# CONTROLADOR-V1-RELES.net
KiCad netlist of a schematic drawn in Altium Designer
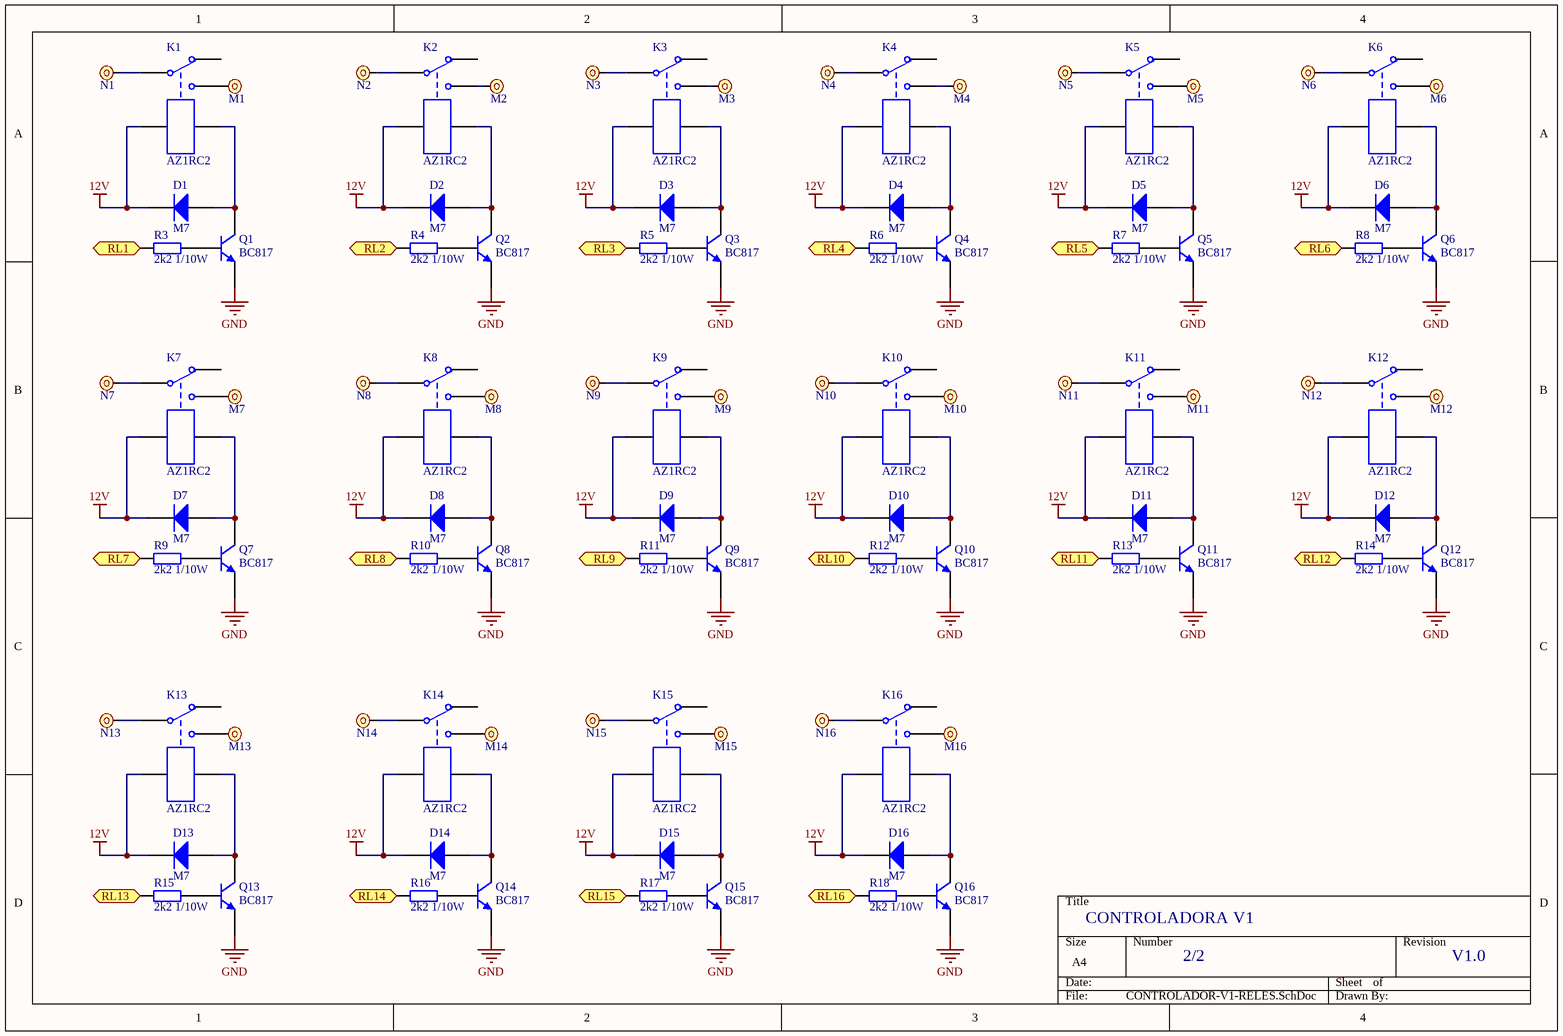
[diagram p0: CONTROLADOR-V1-RELES.SchDoc]

(export (version "E")
  (design (tool "Eeschema 10.0.6"))
  (components
    (comp (ref "D1")
      (value "M7")
      (footprint "Lib SMD:DO-214AC - SMA")
      (description "DIODE GEN PURP 1KV 1A DO214AC")
      (fields (field (name "MANUFACTURER") "Kingtronics"))
      (libsource (lib "Lib SMD") (part "Diodo M7"))
    )
    (comp (ref "D2")
      (value "M7")
      (footprint "Lib SMD:DO-214AC - SMA")
      (description "DIODE GEN PURP 1KV 1A DO214AC")
      (fields (field (name "MANUFACTURER") "Kingtronics"))
      (libsource (lib "Lib SMD") (part "Diodo M7"))
    )
    (comp (ref "D3")
      (value "M7")
      (footprint "Lib SMD:DO-214AC - SMA")
      (description "DIODE GEN PURP 1KV 1A DO214AC")
      (fields (field (name "MANUFACTURER") "Kingtronics"))
      (libsource (lib "Lib SMD") (part "Diodo M7"))
    )
    (comp (ref "D4")
      (value "M7")
      (footprint "Lib SMD:DO-214AC - SMA")
      (description "DIODE GEN PURP 1KV 1A DO214AC")
      (fields (field (name "MANUFACTURER") "Kingtronics"))
      (libsource (lib "Lib SMD") (part "Diodo M7"))
    )
    (comp (ref "D5")
      (value "M7")
      (footprint "Lib SMD:DO-214AC - SMA")
      (description "DIODE GEN PURP 1KV 1A DO214AC")
      (fields (field (name "MANUFACTURER") "Kingtronics"))
      (libsource (lib "Lib SMD") (part "Diodo M7"))
    )
    (comp (ref "D6")
      (value "M7")
      (footprint "Lib SMD:DO-214AC - SMA")
      (description "DIODE GEN PURP 1KV 1A DO214AC")
      (fields (field (name "MANUFACTURER") "Kingtronics"))
      (libsource (lib "Lib SMD") (part "Diodo M7"))
    )
    (comp (ref "D7")
      (value "M7")
      (footprint "Lib SMD:DO-214AC - SMA")
      (description "DIODE GEN PURP 1KV 1A DO214AC")
      (fields (field (name "MANUFACTURER") "Kingtronics"))
      (libsource (lib "Lib SMD") (part "Diodo M7"))
    )
    (comp (ref "D8")
      (value "M7")
      (footprint "Lib SMD:DO-214AC - SMA")
      (description "DIODE GEN PURP 1KV 1A DO214AC")
      (fields (field (name "MANUFACTURER") "Kingtronics"))
      (libsource (lib "Lib SMD") (part "Diodo M7"))
    )
    (comp (ref "D9")
      (value "M7")
      (footprint "Lib SMD:DO-214AC - SMA")
      (description "DIODE GEN PURP 1KV 1A DO214AC")
      (fields (field (name "MANUFACTURER") "Kingtronics"))
      (libsource (lib "Lib SMD") (part "Diodo M7"))
    )
    (comp (ref "D10")
      (value "M7")
      (footprint "Lib SMD:DO-214AC - SMA")
      (description "DIODE GEN PURP 1KV 1A DO214AC")
      (fields (field (name "MANUFACTURER") "Kingtronics"))
      (libsource (lib "Lib SMD") (part "Diodo M7"))
    )
    (comp (ref "D11")
      (value "M7")
      (footprint "Lib SMD:DO-214AC - SMA")
      (description "DIODE GEN PURP 1KV 1A DO214AC")
      (fields (field (name "MANUFACTURER") "Kingtronics"))
      (libsource (lib "Lib SMD") (part "Diodo M7"))
    )
    (comp (ref "D12")
      (value "M7")
      (footprint "Lib SMD:DO-214AC - SMA")
      (description "DIODE GEN PURP 1KV 1A DO214AC")
      (fields (field (name "MANUFACTURER") "Kingtronics"))
      (libsource (lib "Lib SMD") (part "Diodo M7"))
    )
    (comp (ref "D13")
      (value "M7")
      (footprint "Lib SMD:DO-214AC - SMA")
      (description "DIODE GEN PURP 1KV 1A DO214AC")
      (fields (field (name "MANUFACTURER") "Kingtronics"))
      (libsource (lib "Lib SMD") (part "Diodo M7"))
    )
    (comp (ref "D14")
      (value "M7")
      (footprint "Lib SMD:DO-214AC - SMA")
      (description "DIODE GEN PURP 1KV 1A DO214AC")
      (fields (field (name "MANUFACTURER") "Kingtronics"))
      (libsource (lib "Lib SMD") (part "Diodo M7"))
    )
    (comp (ref "D15")
      (value "M7")
      (footprint "Lib SMD:DO-214AC - SMA")
      (description "DIODE GEN PURP 1KV 1A DO214AC")
      (fields (field (name "MANUFACTURER") "Kingtronics"))
      (libsource (lib "Lib SMD") (part "Diodo M7"))
    )
    (comp (ref "D16")
      (value "M7")
      (footprint "Lib SMD:DO-214AC - SMA")
      (description "DIODE GEN PURP 1KV 1A DO214AC")
      (fields (field (name "MANUFACTURER") "Kingtronics"))
      (libsource (lib "Lib SMD") (part "Diodo M7"))
    )
    (comp (ref "K1")
      (value "AZ1RC2")
      (footprint "Lib PTH:RELE SPDT")
      (description "RELAY GEN PURPOSE SPDT 10A 12V")
      (fields (field (name "MANUFACTURER") "Metaltex"))
      (libsource (lib "Lib PTH") (part "Rele AZ1RC2"))
    )
    (comp (ref "K2")
      (value "AZ1RC2")
      (footprint "Lib PTH:RELE SPDT")
      (description "RELAY GEN PURPOSE SPDT 10A 12V")
      (fields (field (name "MANUFACTURER") "Metaltex"))
      (libsource (lib "Lib PTH") (part "Rele AZ1RC2"))
    )
    (comp (ref "K3")
      (value "AZ1RC2")
      (footprint "Lib PTH:RELE SPDT")
      (description "RELAY GEN PURPOSE SPDT 10A 12V")
      (fields (field (name "MANUFACTURER") "Metaltex"))
      (libsource (lib "Lib PTH") (part "Rele AZ1RC2"))
    )
    (comp (ref "K4")
      (value "AZ1RC2")
      (footprint "Lib PTH:RELE SPDT")
      (description "RELAY GEN PURPOSE SPDT 10A 12V")
      (fields (field (name "MANUFACTURER") "Metaltex"))
      (libsource (lib "Lib PTH") (part "Rele AZ1RC2"))
    )
    (comp (ref "K5")
      (value "AZ1RC2")
      (footprint "Lib PTH:RELE SPDT")
      (description "RELAY GEN PURPOSE SPDT 10A 12V")
      (fields (field (name "MANUFACTURER") "Metaltex"))
      (libsource (lib "Lib PTH") (part "Rele AZ1RC2"))
    )
    (comp (ref "K6")
      (value "AZ1RC2")
      (footprint "Lib PTH:RELE SPDT")
      (description "RELAY GEN PURPOSE SPDT 10A 12V")
      (fields (field (name "MANUFACTURER") "Metaltex"))
      (libsource (lib "Lib PTH") (part "Rele AZ1RC2"))
    )
    (comp (ref "K7")
      (value "AZ1RC2")
      (footprint "Lib PTH:RELE SPDT")
      (description "RELAY GEN PURPOSE SPDT 10A 12V")
      (fields (field (name "MANUFACTURER") "Metaltex"))
      (libsource (lib "Lib PTH") (part "Rele AZ1RC2"))
    )
    (comp (ref "K8")
      (value "AZ1RC2")
      (footprint "Lib PTH:RELE SPDT")
      (description "RELAY GEN PURPOSE SPDT 10A 12V")
      (fields (field (name "MANUFACTURER") "Metaltex"))
      (libsource (lib "Lib PTH") (part "Rele AZ1RC2"))
    )
    (comp (ref "K9")
      (value "AZ1RC2")
      (footprint "Lib PTH:RELE SPDT")
      (description "RELAY GEN PURPOSE SPDT 10A 12V")
      (fields (field (name "MANUFACTURER") "Metaltex"))
      (libsource (lib "Lib PTH") (part "Rele AZ1RC2"))
    )
    (comp (ref "K10")
      (value "AZ1RC2")
      (footprint "Lib PTH:RELE SPDT")
      (description "RELAY GEN PURPOSE SPDT 10A 12V")
      (fields (field (name "MANUFACTURER") "Metaltex"))
      (libsource (lib "Lib PTH") (part "Rele AZ1RC2"))
    )
    (comp (ref "K11")
      (value "AZ1RC2")
      (footprint "Lib PTH:RELE SPDT")
      (description "RELAY GEN PURPOSE SPDT 10A 12V")
      (fields (field (name "MANUFACTURER") "Metaltex"))
      (libsource (lib "Lib PTH") (part "Rele AZ1RC2"))
    )
    (comp (ref "K12")
      (value "AZ1RC2")
      (footprint "Lib PTH:RELE SPDT")
      (description "RELAY GEN PURPOSE SPDT 10A 12V")
      (fields (field (name "MANUFACTURER") "Metaltex"))
      (libsource (lib "Lib PTH") (part "Rele AZ1RC2"))
    )
    (comp (ref "K13")
      (value "AZ1RC2")
      (footprint "Lib PTH:RELE SPDT")
      (description "RELAY GEN PURPOSE SPDT 10A 12V")
      (fields (field (name "MANUFACTURER") "Metaltex"))
      (libsource (lib "Lib PTH") (part "Rele AZ1RC2"))
    )
    (comp (ref "K14")
      (value "AZ1RC2")
      (footprint "Lib PTH:RELE SPDT")
      (description "RELAY GEN PURPOSE SPDT 10A 12V")
      (fields (field (name "MANUFACTURER") "Metaltex"))
      (libsource (lib "Lib PTH") (part "Rele AZ1RC2"))
    )
    (comp (ref "K15")
      (value "AZ1RC2")
      (footprint "Lib PTH:RELE SPDT")
      (description "RELAY GEN PURPOSE SPDT 10A 12V")
      (fields (field (name "MANUFACTURER") "Metaltex"))
      (libsource (lib "Lib PTH") (part "Rele AZ1RC2"))
    )
    (comp (ref "K16")
      (value "AZ1RC2")
      (footprint "Lib PTH:RELE SPDT")
      (description "RELAY GEN PURPOSE SPDT 10A 12V")
      (fields (field (name "MANUFACTURER") "Metaltex"))
      (libsource (lib "Lib PTH") (part "Rele AZ1RC2"))
    )
    (comp (ref "M1")
      (value "PAD 1.5x3mm")
      (footprint "Lib PTH:PAD 1.5x3mm")
      (description "PAD")
      (libsource (lib "Lib PTH") (part "PAD 1.5x3mm"))
    )
    (comp (ref "M2")
      (value "PAD 1.5x3mm")
      (footprint "Lib PTH:PAD 1.5x3mm")
      (description "PAD")
      (libsource (lib "Lib PTH") (part "PAD 1.5x3mm"))
    )
    (comp (ref "M3")
      (value "PAD 1.5x3mm")
      (footprint "Lib PTH:PAD 1.5x3mm")
      (description "PAD")
      (libsource (lib "Lib PTH") (part "PAD 1.5x3mm"))
    )
    (comp (ref "M4")
      (value "PAD 1.5x3mm")
      (footprint "Lib PTH:PAD 1.5x3mm")
      (description "PAD")
      (libsource (lib "Lib PTH") (part "PAD 1.5x3mm"))
    )
    (comp (ref "M5")
      (value "PAD 1.5x3mm")
      (footprint "Lib PTH:PAD 1.5x3mm")
      (description "PAD")
      (libsource (lib "Lib PTH") (part "PAD 1.5x3mm"))
    )
    (comp (ref "M6")
      (value "PAD 1.5x3mm")
      (footprint "Lib PTH:PAD 1.5x3mm")
      (description "PAD")
      (libsource (lib "Lib PTH") (part "PAD 1.5x3mm"))
    )
    (comp (ref "M7")
      (value "PAD 1.5x3mm")
      (footprint "Lib PTH:PAD 1.5x3mm")
      (description "PAD")
      (libsource (lib "Lib PTH") (part "PAD 1.5x3mm"))
    )
    (comp (ref "M8")
      (value "PAD 1.5x3mm")
      (footprint "Lib PTH:PAD 1.5x3mm")
      (description "PAD")
      (libsource (lib "Lib PTH") (part "PAD 1.5x3mm"))
    )
    (comp (ref "M9")
      (value "PAD 1.5x3mm")
      (footprint "Lib PTH:PAD 1.5x3mm")
      (description "PAD")
      (libsource (lib "Lib PTH") (part "PAD 1.5x3mm"))
    )
    (comp (ref "M10")
      (value "PAD 1.5x3mm")
      (footprint "Lib PTH:PAD 1.5x3mm")
      (description "PAD")
      (libsource (lib "Lib PTH") (part "PAD 1.5x3mm"))
    )
    (comp (ref "M11")
      (value "PAD 1.5x3mm")
      (footprint "Lib PTH:PAD 1.5x3mm")
      (description "PAD")
      (libsource (lib "Lib PTH") (part "PAD 1.5x3mm"))
    )
    (comp (ref "M12")
      (value "PAD 1.5x3mm")
      (footprint "Lib PTH:PAD 1.5x3mm")
      (description "PAD")
      (libsource (lib "Lib PTH") (part "PAD 1.5x3mm"))
    )
    (comp (ref "M13")
      (value "PAD 1.5x3mm")
      (footprint "Lib PTH:PAD 1.5x3mm")
      (description "PAD")
      (libsource (lib "Lib PTH") (part "PAD 1.5x3mm"))
    )
    (comp (ref "M14")
      (value "PAD 1.5x3mm")
      (footprint "Lib PTH:PAD 1.5x3mm")
      (description "PAD")
      (libsource (lib "Lib PTH") (part "PAD 1.5x3mm"))
    )
    (comp (ref "M15")
      (value "PAD 1.5x3mm")
      (footprint "Lib PTH:PAD 1.5x3mm")
      (description "PAD")
      (libsource (lib "Lib PTH") (part "PAD 1.5x3mm"))
    )
    (comp (ref "M16")
      (value "PAD 1.5x3mm")
      (footprint "Lib PTH:PAD 1.5x3mm")
      (description "PAD")
      (libsource (lib "Lib PTH") (part "PAD 1.5x3mm"))
    )
    (comp (ref "N1")
      (value "PAD 1.5x3mm")
      (footprint "Lib PTH:PAD 1.5x3mm")
      (description "PAD")
      (libsource (lib "Lib PTH") (part "PAD 1.5x3mm"))
    )
    (comp (ref "N2")
      (value "PAD 1.5x3mm")
      (footprint "Lib PTH:PAD 1.5x3mm")
      (description "PAD")
      (libsource (lib "Lib PTH") (part "PAD 1.5x3mm"))
    )
    (comp (ref "N3")
      (value "PAD 1.5x3mm")
      (footprint "Lib PTH:PAD 1.5x3mm")
      (description "PAD")
      (libsource (lib "Lib PTH") (part "PAD 1.5x3mm"))
    )
    (comp (ref "N4")
      (value "PAD 1.5x3mm")
      (footprint "Lib PTH:PAD 1.5x3mm")
      (description "PAD")
      (libsource (lib "Lib PTH") (part "PAD 1.5x3mm"))
    )
    (comp (ref "N5")
      (value "PAD 1.5x3mm")
      (footprint "Lib PTH:PAD 1.5x3mm")
      (description "PAD")
      (libsource (lib "Lib PTH") (part "PAD 1.5x3mm"))
    )
    (comp (ref "N6")
      (value "PAD 1.5x3mm")
      (footprint "Lib PTH:PAD 1.5x3mm")
      (description "PAD")
      (libsource (lib "Lib PTH") (part "PAD 1.5x3mm"))
    )
    (comp (ref "N7")
      (value "PAD 1.5x3mm")
      (footprint "Lib PTH:PAD 1.5x3mm")
      (description "PAD")
      (libsource (lib "Lib PTH") (part "PAD 1.5x3mm"))
    )
    (comp (ref "N8")
      (value "PAD 1.5x3mm")
      (footprint "Lib PTH:PAD 1.5x3mm")
      (description "PAD")
      (libsource (lib "Lib PTH") (part "PAD 1.5x3mm"))
    )
    (comp (ref "N9")
      (value "PAD 1.5x3mm")
      (footprint "Lib PTH:PAD 1.5x3mm")
      (description "PAD")
      (libsource (lib "Lib PTH") (part "PAD 1.5x3mm"))
    )
    (comp (ref "N10")
      (value "PAD 1.5x3mm")
      (footprint "Lib PTH:PAD 1.5x3mm")
      (description "PAD")
      (libsource (lib "Lib PTH") (part "PAD 1.5x3mm"))
    )
    (comp (ref "N11")
      (value "PAD 1.5x3mm")
      (footprint "Lib PTH:PAD 1.5x3mm")
      (description "PAD")
      (libsource (lib "Lib PTH") (part "PAD 1.5x3mm"))
    )
    (comp (ref "N12")
      (value "PAD 1.5x3mm")
      (footprint "Lib PTH:PAD 1.5x3mm")
      (description "PAD")
      (libsource (lib "Lib PTH") (part "PAD 1.5x3mm"))
    )
    (comp (ref "N13")
      (value "PAD 1.5x3mm")
      (footprint "Lib PTH:PAD 1.5x3mm")
      (description "PAD")
      (libsource (lib "Lib PTH") (part "PAD 1.5x3mm"))
    )
    (comp (ref "N14")
      (value "PAD 1.5x3mm")
      (footprint "Lib PTH:PAD 1.5x3mm")
      (description "PAD")
      (libsource (lib "Lib PTH") (part "PAD 1.5x3mm"))
    )
    (comp (ref "N15")
      (value "PAD 1.5x3mm")
      (footprint "Lib PTH:PAD 1.5x3mm")
      (description "PAD")
      (libsource (lib "Lib PTH") (part "PAD 1.5x3mm"))
    )
    (comp (ref "N16")
      (value "PAD 1.5x3mm")
      (footprint "Lib PTH:PAD 1.5x3mm")
      (description "PAD")
      (libsource (lib "Lib PTH") (part "PAD 1.5x3mm"))
    )
    (comp (ref "Q1")
      (value "BC817")
      (footprint "Lib SMD:SOT23-3N")
      (description "TRANS NPN 45V 0.5A SOT23")
      (fields
        (field (name "MANUFACTURER") "ON Semiconductor")
        (field (name "MANUFACTURER PART NUMBER") "BC817-25LT1G")
      )
      (libsource (lib "Lib SMD") (part "Transistor NPN BC817"))
    )
    (comp (ref "Q2")
      (value "BC817")
      (footprint "Lib SMD:SOT23-3N")
      (description "TRANS NPN 45V 0.5A SOT23")
      (fields
        (field (name "MANUFACTURER") "ON Semiconductor")
        (field (name "MANUFACTURER PART NUMBER") "BC817-25LT1G")
      )
      (libsource (lib "Lib SMD") (part "Transistor NPN BC817"))
    )
    (comp (ref "Q3")
      (value "BC817")
      (footprint "Lib SMD:SOT23-3N")
      (description "TRANS NPN 45V 0.5A SOT23")
      (fields
        (field (name "MANUFACTURER") "ON Semiconductor")
        (field (name "MANUFACTURER PART NUMBER") "BC817-25LT1G")
      )
      (libsource (lib "Lib SMD") (part "Transistor NPN BC817"))
    )
    (comp (ref "Q4")
      (value "BC817")
      (footprint "Lib SMD:SOT23-3N")
      (description "TRANS NPN 45V 0.5A SOT23")
      (fields
        (field (name "MANUFACTURER") "ON Semiconductor")
        (field (name "MANUFACTURER PART NUMBER") "BC817-25LT1G")
      )
      (libsource (lib "Lib SMD") (part "Transistor NPN BC817"))
    )
    (comp (ref "Q5")
      (value "BC817")
      (footprint "Lib SMD:SOT23-3N")
      (description "TRANS NPN 45V 0.5A SOT23")
      (fields
        (field (name "MANUFACTURER") "ON Semiconductor")
        (field (name "MANUFACTURER PART NUMBER") "BC817-25LT1G")
      )
      (libsource (lib "Lib SMD") (part "Transistor NPN BC817"))
    )
    (comp (ref "Q6")
      (value "BC817")
      (footprint "Lib SMD:SOT23-3N")
      (description "TRANS NPN 45V 0.5A SOT23")
      (fields
        (field (name "MANUFACTURER") "ON Semiconductor")
        (field (name "MANUFACTURER PART NUMBER") "BC817-25LT1G")
      )
      (libsource (lib "Lib SMD") (part "Transistor NPN BC817"))
    )
    (comp (ref "Q7")
      (value "BC817")
      (footprint "Lib SMD:SOT23-3N")
      (description "TRANS NPN 45V 0.5A SOT23")
      (fields
        (field (name "MANUFACTURER") "ON Semiconductor")
        (field (name "MANUFACTURER PART NUMBER") "BC817-25LT1G")
      )
      (libsource (lib "Lib SMD") (part "Transistor NPN BC817"))
    )
    (comp (ref "Q8")
      (value "BC817")
      (footprint "Lib SMD:SOT23-3N")
      (description "TRANS NPN 45V 0.5A SOT23")
      (fields
        (field (name "MANUFACTURER") "ON Semiconductor")
        (field (name "MANUFACTURER PART NUMBER") "BC817-25LT1G")
      )
      (libsource (lib "Lib SMD") (part "Transistor NPN BC817"))
    )
    (comp (ref "Q9")
      (value "BC817")
      (footprint "Lib SMD:SOT23-3N")
      (description "TRANS NPN 45V 0.5A SOT23")
      (fields
        (field (name "MANUFACTURER") "ON Semiconductor")
        (field (name "MANUFACTURER PART NUMBER") "BC817-25LT1G")
      )
      (libsource (lib "Lib SMD") (part "Transistor NPN BC817"))
    )
    (comp (ref "Q10")
      (value "BC817")
      (footprint "Lib SMD:SOT23-3N")
      (description "TRANS NPN 45V 0.5A SOT23")
      (fields
        (field (name "MANUFACTURER") "ON Semiconductor")
        (field (name "MANUFACTURER PART NUMBER") "BC817-25LT1G")
      )
      (libsource (lib "Lib SMD") (part "Transistor NPN BC817"))
    )
    (comp (ref "Q11")
      (value "BC817")
      (footprint "Lib SMD:SOT23-3N")
      (description "TRANS NPN 45V 0.5A SOT23")
      (fields
        (field (name "MANUFACTURER") "ON Semiconductor")
        (field (name "MANUFACTURER PART NUMBER") "BC817-25LT1G")
      )
      (libsource (lib "Lib SMD") (part "Transistor NPN BC817"))
    )
    (comp (ref "Q12")
      (value "BC817")
      (footprint "Lib SMD:SOT23-3N")
      (description "TRANS NPN 45V 0.5A SOT23")
      (fields
        (field (name "MANUFACTURER") "ON Semiconductor")
        (field (name "MANUFACTURER PART NUMBER") "BC817-25LT1G")
      )
      (libsource (lib "Lib SMD") (part "Transistor NPN BC817"))
    )
    (comp (ref "Q13")
      (value "BC817")
      (footprint "Lib SMD:SOT23-3N")
      (description "TRANS NPN 45V 0.5A SOT23")
      (fields
        (field (name "MANUFACTURER") "ON Semiconductor")
        (field (name "MANUFACTURER PART NUMBER") "BC817-25LT1G")
      )
      (libsource (lib "Lib SMD") (part "Transistor NPN BC817"))
    )
    (comp (ref "Q14")
      (value "BC817")
      (footprint "Lib SMD:SOT23-3N")
      (description "TRANS NPN 45V 0.5A SOT23")
      (fields
        (field (name "MANUFACTURER") "ON Semiconductor")
        (field (name "MANUFACTURER PART NUMBER") "BC817-25LT1G")
      )
      (libsource (lib "Lib SMD") (part "Transistor NPN BC817"))
    )
    (comp (ref "Q15")
      (value "BC817")
      (footprint "Lib SMD:SOT23-3N")
      (description "TRANS NPN 45V 0.5A SOT23")
      (fields
        (field (name "MANUFACTURER") "ON Semiconductor")
        (field (name "MANUFACTURER PART NUMBER") "BC817-25LT1G")
      )
      (libsource (lib "Lib SMD") (part "Transistor NPN BC817"))
    )
    (comp (ref "Q16")
      (value "BC817")
      (footprint "Lib SMD:SOT23-3N")
      (description "TRANS NPN 45V 0.5A SOT23")
      (fields
        (field (name "MANUFACTURER") "ON Semiconductor")
        (field (name "MANUFACTURER PART NUMBER") "BC817-25LT1G")
      )
      (libsource (lib "Lib SMD") (part "Transistor NPN BC817"))
    )
    (comp (ref "R3")
      (value "2k2 1/10W")
      (footprint "Lib SMD:RESC0603N")
      (description "RES SMD 2.2K OHM 5% 1/10W 0603")
      (fields
        (field (name "MANUFACTURER") "Stackpole Electronics Inc.")
        (field (name "MANUFACTURER PART NUMBER") "RMCF0603JT2K20")
      )
      (libsource (lib "Lib SMD") (part "Res 2k2 1/10W 5% 0603"))
    )
    (comp (ref "R4")
      (value "2k2 1/10W")
      (footprint "Lib SMD:RESC0603N")
      (description "RES SMD 2.2K OHM 5% 1/10W 0603")
      (fields
        (field (name "MANUFACTURER") "Stackpole Electronics Inc.")
        (field (name "MANUFACTURER PART NUMBER") "RMCF0603JT2K20")
      )
      (libsource (lib "Lib SMD") (part "Res 2k2 1/10W 5% 0603"))
    )
    (comp (ref "R5")
      (value "2k2 1/10W")
      (footprint "Lib SMD:RESC0603N")
      (description "RES SMD 2.2K OHM 5% 1/10W 0603")
      (fields
        (field (name "MANUFACTURER") "Stackpole Electronics Inc.")
        (field (name "MANUFACTURER PART NUMBER") "RMCF0603JT2K20")
      )
      (libsource (lib "Lib SMD") (part "Res 2k2 1/10W 5% 0603"))
    )
    (comp (ref "R6")
      (value "2k2 1/10W")
      (footprint "Lib SMD:RESC0603N")
      (description "RES SMD 2.2K OHM 5% 1/10W 0603")
      (fields
        (field (name "MANUFACTURER") "Stackpole Electronics Inc.")
        (field (name "MANUFACTURER PART NUMBER") "RMCF0603JT2K20")
      )
      (libsource (lib "Lib SMD") (part "Res 2k2 1/10W 5% 0603"))
    )
    (comp (ref "R7")
      (value "2k2 1/10W")
      (footprint "Lib SMD:RESC0603N")
      (description "RES SMD 2.2K OHM 5% 1/10W 0603")
      (fields
        (field (name "MANUFACTURER") "Stackpole Electronics Inc.")
        (field (name "MANUFACTURER PART NUMBER") "RMCF0603JT2K20")
      )
      (libsource (lib "Lib SMD") (part "Res 2k2 1/10W 5% 0603"))
    )
    (comp (ref "R8")
      (value "2k2 1/10W")
      (footprint "Lib SMD:RESC0603N")
      (description "RES SMD 2.2K OHM 5% 1/10W 0603")
      (fields
        (field (name "MANUFACTURER") "Stackpole Electronics Inc.")
        (field (name "MANUFACTURER PART NUMBER") "RMCF0603JT2K20")
      )
      (libsource (lib "Lib SMD") (part "Res 2k2 1/10W 5% 0603"))
    )
    (comp (ref "R9")
      (value "2k2 1/10W")
      (footprint "Lib SMD:RESC0603N")
      (description "RES SMD 2.2K OHM 5% 1/10W 0603")
      (fields
        (field (name "MANUFACTURER") "Stackpole Electronics Inc.")
        (field (name "MANUFACTURER PART NUMBER") "RMCF0603JT2K20")
      )
      (libsource (lib "Lib SMD") (part "Res 2k2 1/10W 5% 0603"))
    )
    (comp (ref "R10")
      (value "2k2 1/10W")
      (footprint "Lib SMD:RESC0603N")
      (description "RES SMD 2.2K OHM 5% 1/10W 0603")
      (fields
        (field (name "MANUFACTURER") "Stackpole Electronics Inc.")
        (field (name "MANUFACTURER PART NUMBER") "RMCF0603JT2K20")
      )
      (libsource (lib "Lib SMD") (part "Res 2k2 1/10W 5% 0603"))
    )
    (comp (ref "R11")
      (value "2k2 1/10W")
      (footprint "Lib SMD:RESC0603N")
      (description "RES SMD 2.2K OHM 5% 1/10W 0603")
      (fields
        (field (name "MANUFACTURER") "Stackpole Electronics Inc.")
        (field (name "MANUFACTURER PART NUMBER") "RMCF0603JT2K20")
      )
      (libsource (lib "Lib SMD") (part "Res 2k2 1/10W 5% 0603"))
    )
    (comp (ref "R12")
      (value "2k2 1/10W")
      (footprint "Lib SMD:RESC0603N")
      (description "RES SMD 2.2K OHM 5% 1/10W 0603")
      (fields
        (field (name "MANUFACTURER") "Stackpole Electronics Inc.")
        (field (name "MANUFACTURER PART NUMBER") "RMCF0603JT2K20")
      )
      (libsource (lib "Lib SMD") (part "Res 2k2 1/10W 5% 0603"))
    )
    (comp (ref "R13")
      (value "2k2 1/10W")
      (footprint "Lib SMD:RESC0603N")
      (description "RES SMD 2.2K OHM 5% 1/10W 0603")
      (fields
        (field (name "MANUFACTURER") "Stackpole Electronics Inc.")
        (field (name "MANUFACTURER PART NUMBER") "RMCF0603JT2K20")
      )
      (libsource (lib "Lib SMD") (part "Res 2k2 1/10W 5% 0603"))
    )
    (comp (ref "R14")
      (value "2k2 1/10W")
      (footprint "Lib SMD:RESC0603N")
      (description "RES SMD 2.2K OHM 5% 1/10W 0603")
      (fields
        (field (name "MANUFACTURER") "Stackpole Electronics Inc.")
        (field (name "MANUFACTURER PART NUMBER") "RMCF0603JT2K20")
      )
      (libsource (lib "Lib SMD") (part "Res 2k2 1/10W 5% 0603"))
    )
    (comp (ref "R15")
      (value "2k2 1/10W")
      (footprint "Lib SMD:RESC0603N")
      (description "RES SMD 2.2K OHM 5% 1/10W 0603")
      (fields
        (field (name "MANUFACTURER") "Stackpole Electronics Inc.")
        (field (name "MANUFACTURER PART NUMBER") "RMCF0603JT2K20")
      )
      (libsource (lib "Lib SMD") (part "Res 2k2 1/10W 5% 0603"))
    )
    (comp (ref "R16")
      (value "2k2 1/10W")
      (footprint "Lib SMD:RESC0603N")
      (description "RES SMD 2.2K OHM 5% 1/10W 0603")
      (fields
        (field (name "MANUFACTURER") "Stackpole Electronics Inc.")
        (field (name "MANUFACTURER PART NUMBER") "RMCF0603JT2K20")
      )
      (libsource (lib "Lib SMD") (part "Res 2k2 1/10W 5% 0603"))
    )
    (comp (ref "R17")
      (value "2k2 1/10W")
      (footprint "Lib SMD:RESC0603N")
      (description "RES SMD 2.2K OHM 5% 1/10W 0603")
      (fields
        (field (name "MANUFACTURER") "Stackpole Electronics Inc.")
        (field (name "MANUFACTURER PART NUMBER") "RMCF0603JT2K20")
      )
      (libsource (lib "Lib SMD") (part "Res 2k2 1/10W 5% 0603"))
    )
    (comp (ref "R18")
      (value "2k2 1/10W")
      (footprint "Lib SMD:RESC0603N")
      (description "RES SMD 2.2K OHM 5% 1/10W 0603")
      (fields
        (field (name "MANUFACTURER") "Stackpole Electronics Inc.")
        (field (name "MANUFACTURER PART NUMBER") "RMCF0603JT2K20")
      )
      (libsource (lib "Lib SMD") (part "Res 2k2 1/10W 5% 0603"))
    )
  )
  (nets
    (net (code "1") (name "/RL1") (class "Default")
      (node (ref "R3") (pin "1") (pinfunction "1_1") (pintype "passive"))
    )
    (net (code "2") (name "/RL2") (class "Default")
      (node (ref "R4") (pin "1") (pinfunction "1_1") (pintype "passive"))
    )
    (net (code "3") (name "/RL3") (class "Default")
      (node (ref "R5") (pin "1") (pinfunction "1_1") (pintype "passive"))
    )
    (net (code "4") (name "/RL4") (class "Default")
      (node (ref "R6") (pin "1") (pinfunction "1_1") (pintype "passive"))
    )
    (net (code "5") (name "/RL5") (class "Default")
      (node (ref "R7") (pin "1") (pinfunction "1_1") (pintype "passive"))
    )
    (net (code "6") (name "/RL6") (class "Default")
      (node (ref "R8") (pin "1") (pinfunction "1_1") (pintype "passive"))
    )
    (net (code "7") (name "/RL7") (class "Default")
      (node (ref "R9") (pin "1") (pinfunction "1_1") (pintype "passive"))
    )
    (net (code "8") (name "/RL8") (class "Default")
      (node (ref "R10") (pin "1") (pinfunction "1_1") (pintype "passive"))
    )
    (net (code "9") (name "/RL9") (class "Default")
      (node (ref "R11") (pin "1") (pinfunction "1_1") (pintype "passive"))
    )
    (net (code "10") (name "/RL10") (class "Default")
      (node (ref "R12") (pin "1") (pinfunction "1_1") (pintype "passive"))
    )
    (net (code "11") (name "/RL11") (class "Default")
      (node (ref "R13") (pin "1") (pinfunction "1_1") (pintype "passive"))
    )
    (net (code "12") (name "/RL12") (class "Default")
      (node (ref "R14") (pin "1") (pinfunction "1_1") (pintype "passive"))
    )
    (net (code "13") (name "/RL13") (class "Default")
      (node (ref "R15") (pin "1") (pinfunction "1_1") (pintype "passive"))
    )
    (net (code "14") (name "/RL14") (class "Default")
      (node (ref "R16") (pin "1") (pinfunction "1_1") (pintype "passive"))
    )
    (net (code "15") (name "/RL15") (class "Default")
      (node (ref "R17") (pin "1") (pinfunction "1_1") (pintype "passive"))
    )
    (net (code "16") (name "/RL16") (class "Default")
      (node (ref "R18") (pin "1") (pinfunction "1_1") (pintype "passive"))
    )
    (net (code "17") (name "12V") (class "Default")
      (node (ref "D1") (pin "1") (pinfunction "K_1") (pintype "passive"))
      (node (ref "D10") (pin "1") (pinfunction "K_1") (pintype "passive"))
      (node (ref "D11") (pin "1") (pinfunction "K_1") (pintype "passive"))
      (node (ref "D12") (pin "1") (pinfunction "K_1") (pintype "passive"))
      (node (ref "D13") (pin "1") (pinfunction "K_1") (pintype "passive"))
      (node (ref "D14") (pin "1") (pinfunction "K_1") (pintype "passive"))
      (node (ref "D15") (pin "1") (pinfunction "K_1") (pintype "passive"))
      (node (ref "D16") (pin "1") (pinfunction "K_1") (pintype "passive"))
      (node (ref "D2") (pin "1") (pinfunction "K_1") (pintype "passive"))
      (node (ref "D3") (pin "1") (pinfunction "K_1") (pintype "passive"))
      (node (ref "D4") (pin "1") (pinfunction "K_1") (pintype "passive"))
      (node (ref "D5") (pin "1") (pinfunction "K_1") (pintype "passive"))
      (node (ref "D6") (pin "1") (pinfunction "K_1") (pintype "passive"))
      (node (ref "D7") (pin "1") (pinfunction "K_1") (pintype "passive"))
      (node (ref "D8") (pin "1") (pinfunction "K_1") (pintype "passive"))
      (node (ref "D9") (pin "1") (pinfunction "K_1") (pintype "passive"))
      (node (ref "K1") (pin "4") (pinfunction "4_4") (pintype "passive"))
      (node (ref "K10") (pin "4") (pinfunction "4_4") (pintype "passive"))
      (node (ref "K11") (pin "4") (pinfunction "4_4") (pintype "passive"))
      (node (ref "K12") (pin "4") (pinfunction "4_4") (pintype "passive"))
      (node (ref "K13") (pin "4") (pinfunction "4_4") (pintype "passive"))
      (node (ref "K14") (pin "4") (pinfunction "4_4") (pintype "passive"))
      (node (ref "K15") (pin "4") (pinfunction "4_4") (pintype "passive"))
      (node (ref "K16") (pin "4") (pinfunction "4_4") (pintype "passive"))
      (node (ref "K2") (pin "4") (pinfunction "4_4") (pintype "passive"))
      (node (ref "K3") (pin "4") (pinfunction "4_4") (pintype "passive"))
      (node (ref "K4") (pin "4") (pinfunction "4_4") (pintype "passive"))
      (node (ref "K5") (pin "4") (pinfunction "4_4") (pintype "passive"))
      (node (ref "K6") (pin "4") (pinfunction "4_4") (pintype "passive"))
      (node (ref "K7") (pin "4") (pinfunction "4_4") (pintype "passive"))
      (node (ref "K8") (pin "4") (pinfunction "4_4") (pintype "passive"))
      (node (ref "K9") (pin "4") (pinfunction "4_4") (pintype "passive"))
    )
    (net (code "18") (name "GND") (class "Default")
      (node (ref "Q1") (pin "2") (pinfunction "E_2") (pintype "passive"))
      (node (ref "Q10") (pin "2") (pinfunction "E_2") (pintype "passive"))
      (node (ref "Q11") (pin "2") (pinfunction "E_2") (pintype "passive"))
      (node (ref "Q12") (pin "2") (pinfunction "E_2") (pintype "passive"))
      (node (ref "Q13") (pin "2") (pinfunction "E_2") (pintype "passive"))
      (node (ref "Q14") (pin "2") (pinfunction "E_2") (pintype "passive"))
      (node (ref "Q15") (pin "2") (pinfunction "E_2") (pintype "passive"))
      (node (ref "Q16") (pin "2") (pinfunction "E_2") (pintype "passive"))
      (node (ref "Q2") (pin "2") (pinfunction "E_2") (pintype "passive"))
      (node (ref "Q3") (pin "2") (pinfunction "E_2") (pintype "passive"))
      (node (ref "Q4") (pin "2") (pinfunction "E_2") (pintype "passive"))
      (node (ref "Q5") (pin "2") (pinfunction "E_2") (pintype "passive"))
      (node (ref "Q6") (pin "2") (pinfunction "E_2") (pintype "passive"))
      (node (ref "Q7") (pin "2") (pinfunction "E_2") (pintype "passive"))
      (node (ref "Q8") (pin "2") (pinfunction "E_2") (pintype "passive"))
      (node (ref "Q9") (pin "2") (pinfunction "E_2") (pintype "passive"))
    )
    (net (code "19") (name "Net-(D1-A)") (class "Default")
      (node (ref "D1") (pin "2") (pinfunction "A_2") (pintype "passive"))
      (node (ref "K1") (pin "5") (pinfunction "5_5") (pintype "passive"))
      (node (ref "Q1") (pin "3") (pinfunction "C_3") (pintype "passive"))
    )
    (net (code "20") (name "Net-(D2-A)") (class "Default")
      (node (ref "D2") (pin "2") (pinfunction "A_2") (pintype "passive"))
      (node (ref "K2") (pin "5") (pinfunction "5_5") (pintype "passive"))
      (node (ref "Q2") (pin "3") (pinfunction "C_3") (pintype "passive"))
    )
    (net (code "21") (name "Net-(D3-A)") (class "Default")
      (node (ref "D3") (pin "2") (pinfunction "A_2") (pintype "passive"))
      (node (ref "K3") (pin "5") (pinfunction "5_5") (pintype "passive"))
      (node (ref "Q3") (pin "3") (pinfunction "C_3") (pintype "passive"))
    )
    (net (code "22") (name "Net-(D4-A)") (class "Default")
      (node (ref "D4") (pin "2") (pinfunction "A_2") (pintype "passive"))
      (node (ref "K4") (pin "5") (pinfunction "5_5") (pintype "passive"))
      (node (ref "Q4") (pin "3") (pinfunction "C_3") (pintype "passive"))
    )
    (net (code "23") (name "Net-(D5-A)") (class "Default")
      (node (ref "D5") (pin "2") (pinfunction "A_2") (pintype "passive"))
      (node (ref "K5") (pin "5") (pinfunction "5_5") (pintype "passive"))
      (node (ref "Q5") (pin "3") (pinfunction "C_3") (pintype "passive"))
    )
    (net (code "24") (name "Net-(D6-A)") (class "Default")
      (node (ref "D6") (pin "2") (pinfunction "A_2") (pintype "passive"))
      (node (ref "K6") (pin "5") (pinfunction "5_5") (pintype "passive"))
      (node (ref "Q6") (pin "3") (pinfunction "C_3") (pintype "passive"))
    )
    (net (code "25") (name "Net-(D7-A)") (class "Default")
      (node (ref "D7") (pin "2") (pinfunction "A_2") (pintype "passive"))
      (node (ref "K7") (pin "5") (pinfunction "5_5") (pintype "passive"))
      (node (ref "Q7") (pin "3") (pinfunction "C_3") (pintype "passive"))
    )
    (net (code "26") (name "Net-(D8-A)") (class "Default")
      (node (ref "D8") (pin "2") (pinfunction "A_2") (pintype "passive"))
      (node (ref "K8") (pin "5") (pinfunction "5_5") (pintype "passive"))
      (node (ref "Q8") (pin "3") (pinfunction "C_3") (pintype "passive"))
    )
    (net (code "27") (name "Net-(D9-A)") (class "Default")
      (node (ref "D9") (pin "2") (pinfunction "A_2") (pintype "passive"))
      (node (ref "K9") (pin "5") (pinfunction "5_5") (pintype "passive"))
      (node (ref "Q9") (pin "3") (pinfunction "C_3") (pintype "passive"))
    )
    (net (code "28") (name "Net-(D10-A)") (class "Default")
      (node (ref "D10") (pin "2") (pinfunction "A_2") (pintype "passive"))
      (node (ref "K10") (pin "5") (pinfunction "5_5") (pintype "passive"))
      (node (ref "Q10") (pin "3") (pinfunction "C_3") (pintype "passive"))
    )
    (net (code "29") (name "Net-(D11-A)") (class "Default")
      (node (ref "D11") (pin "2") (pinfunction "A_2") (pintype "passive"))
      (node (ref "K11") (pin "5") (pinfunction "5_5") (pintype "passive"))
      (node (ref "Q11") (pin "3") (pinfunction "C_3") (pintype "passive"))
    )
    (net (code "30") (name "Net-(D12-A)") (class "Default")
      (node (ref "D12") (pin "2") (pinfunction "A_2") (pintype "passive"))
      (node (ref "K12") (pin "5") (pinfunction "5_5") (pintype "passive"))
      (node (ref "Q12") (pin "3") (pinfunction "C_3") (pintype "passive"))
    )
    (net (code "31") (name "Net-(D13-A)") (class "Default")
      (node (ref "D13") (pin "2") (pinfunction "A_2") (pintype "passive"))
      (node (ref "K13") (pin "5") (pinfunction "5_5") (pintype "passive"))
      (node (ref "Q13") (pin "3") (pinfunction "C_3") (pintype "passive"))
    )
    (net (code "32") (name "Net-(D14-A)") (class "Default")
      (node (ref "D14") (pin "2") (pinfunction "A_2") (pintype "passive"))
      (node (ref "K14") (pin "5") (pinfunction "5_5") (pintype "passive"))
      (node (ref "Q14") (pin "3") (pinfunction "C_3") (pintype "passive"))
    )
    (net (code "33") (name "Net-(D15-A)") (class "Default")
      (node (ref "D15") (pin "2") (pinfunction "A_2") (pintype "passive"))
      (node (ref "K15") (pin "5") (pinfunction "5_5") (pintype "passive"))
      (node (ref "Q15") (pin "3") (pinfunction "C_3") (pintype "passive"))
    )
    (net (code "34") (name "Net-(D16-A)") (class "Default")
      (node (ref "D16") (pin "2") (pinfunction "A_2") (pintype "passive"))
      (node (ref "K16") (pin "5") (pinfunction "5_5") (pintype "passive"))
      (node (ref "Q16") (pin "3") (pinfunction "C_3") (pintype "passive"))
    )
    (net (code "35") (name "Net-(K1-Comum)") (class "Default")
      (node (ref "K1") (pin "1") (pinfunction "Comum_1") (pintype "passive"))
      (node (ref "N1") (pin "1") (pinfunction "1_1") (pintype "passive"))
    )
    (net (code "36") (name "Net-(K1-N.A.)") (class "Default")
      (node (ref "K1") (pin "2") (pinfunction "N.A._2") (pintype "passive"))
      (node (ref "M1") (pin "1") (pinfunction "1_1") (pintype "passive"))
    )
    (net (code "37") (name "Net-(K2-Comum)") (class "Default")
      (node (ref "K2") (pin "1") (pinfunction "Comum_1") (pintype "passive"))
      (node (ref "N2") (pin "1") (pinfunction "1_1") (pintype "passive"))
    )
    (net (code "38") (name "Net-(K2-N.A.)") (class "Default")
      (node (ref "K2") (pin "2") (pinfunction "N.A._2") (pintype "passive"))
      (node (ref "M2") (pin "1") (pinfunction "1_1") (pintype "passive"))
    )
    (net (code "39") (name "Net-(K3-Comum)") (class "Default")
      (node (ref "K3") (pin "1") (pinfunction "Comum_1") (pintype "passive"))
      (node (ref "N3") (pin "1") (pinfunction "1_1") (pintype "passive"))
    )
    (net (code "40") (name "Net-(K3-N.A.)") (class "Default")
      (node (ref "K3") (pin "2") (pinfunction "N.A._2") (pintype "passive"))
      (node (ref "M3") (pin "1") (pinfunction "1_1") (pintype "passive"))
    )
    (net (code "41") (name "Net-(K4-Comum)") (class "Default")
      (node (ref "K4") (pin "1") (pinfunction "Comum_1") (pintype "passive"))
      (node (ref "N4") (pin "1") (pinfunction "1_1") (pintype "passive"))
    )
    (net (code "42") (name "Net-(K4-N.A.)") (class "Default")
      (node (ref "K4") (pin "2") (pinfunction "N.A._2") (pintype "passive"))
      (node (ref "M4") (pin "1") (pinfunction "1_1") (pintype "passive"))
    )
    (net (code "43") (name "Net-(K5-Comum)") (class "Default")
      (node (ref "K5") (pin "1") (pinfunction "Comum_1") (pintype "passive"))
      (node (ref "N5") (pin "1") (pinfunction "1_1") (pintype "passive"))
    )
    (net (code "44") (name "Net-(K5-N.A.)") (class "Default")
      (node (ref "K5") (pin "2") (pinfunction "N.A._2") (pintype "passive"))
      (node (ref "M5") (pin "1") (pinfunction "1_1") (pintype "passive"))
    )
    (net (code "45") (name "Net-(K6-Comum)") (class "Default")
      (node (ref "K6") (pin "1") (pinfunction "Comum_1") (pintype "passive"))
      (node (ref "N6") (pin "1") (pinfunction "1_1") (pintype "passive"))
    )
    (net (code "46") (name "Net-(K6-N.A.)") (class "Default")
      (node (ref "K6") (pin "2") (pinfunction "N.A._2") (pintype "passive"))
      (node (ref "M6") (pin "1") (pinfunction "1_1") (pintype "passive"))
    )
    (net (code "47") (name "Net-(K7-Comum)") (class "Default")
      (node (ref "K7") (pin "1") (pinfunction "Comum_1") (pintype "passive"))
      (node (ref "N7") (pin "1") (pinfunction "1_1") (pintype "passive"))
    )
    (net (code "48") (name "Net-(K7-N.A.)") (class "Default")
      (node (ref "K7") (pin "2") (pinfunction "N.A._2") (pintype "passive"))
      (node (ref "M7") (pin "1") (pinfunction "1_1") (pintype "passive"))
    )
    (net (code "49") (name "Net-(K8-Comum)") (class "Default")
      (node (ref "K8") (pin "1") (pinfunction "Comum_1") (pintype "passive"))
      (node (ref "N8") (pin "1") (pinfunction "1_1") (pintype "passive"))
    )
    (net (code "50") (name "Net-(K8-N.A.)") (class "Default")
      (node (ref "K8") (pin "2") (pinfunction "N.A._2") (pintype "passive"))
      (node (ref "M8") (pin "1") (pinfunction "1_1") (pintype "passive"))
    )
    (net (code "51") (name "Net-(K9-Comum)") (class "Default")
      (node (ref "K9") (pin "1") (pinfunction "Comum_1") (pintype "passive"))
      (node (ref "N9") (pin "1") (pinfunction "1_1") (pintype "passive"))
    )
    (net (code "52") (name "Net-(K9-N.A.)") (class "Default")
      (node (ref "K9") (pin "2") (pinfunction "N.A._2") (pintype "passive"))
      (node (ref "M9") (pin "1") (pinfunction "1_1") (pintype "passive"))
    )
    (net (code "53") (name "Net-(K10-Comum)") (class "Default")
      (node (ref "K10") (pin "1") (pinfunction "Comum_1") (pintype "passive"))
      (node (ref "N10") (pin "1") (pinfunction "1_1") (pintype "passive"))
    )
    (net (code "54") (name "Net-(K10-N.A.)") (class "Default")
      (node (ref "K10") (pin "2") (pinfunction "N.A._2") (pintype "passive"))
      (node (ref "M10") (pin "1") (pinfunction "1_1") (pintype "passive"))
    )
    (net (code "55") (name "Net-(K11-Comum)") (class "Default")
      (node (ref "K11") (pin "1") (pinfunction "Comum_1") (pintype "passive"))
      (node (ref "N11") (pin "1") (pinfunction "1_1") (pintype "passive"))
    )
    (net (code "56") (name "Net-(K11-N.A.)") (class "Default")
      (node (ref "K11") (pin "2") (pinfunction "N.A._2") (pintype "passive"))
      (node (ref "M11") (pin "1") (pinfunction "1_1") (pintype "passive"))
    )
    (net (code "57") (name "Net-(K12-Comum)") (class "Default")
      (node (ref "K12") (pin "1") (pinfunction "Comum_1") (pintype "passive"))
      (node (ref "N12") (pin "1") (pinfunction "1_1") (pintype "passive"))
    )
    (net (code "58") (name "Net-(K12-N.A.)") (class "Default")
      (node (ref "K12") (pin "2") (pinfunction "N.A._2") (pintype "passive"))
      (node (ref "M12") (pin "1") (pinfunction "1_1") (pintype "passive"))
    )
    (net (code "59") (name "Net-(K13-Comum)") (class "Default")
      (node (ref "K13") (pin "1") (pinfunction "Comum_1") (pintype "passive"))
      (node (ref "N13") (pin "1") (pinfunction "1_1") (pintype "passive"))
    )
    (net (code "60") (name "Net-(K13-N.A.)") (class "Default")
      (node (ref "K13") (pin "2") (pinfunction "N.A._2") (pintype "passive"))
      (node (ref "M13") (pin "1") (pinfunction "1_1") (pintype "passive"))
    )
    (net (code "61") (name "Net-(K14-Comum)") (class "Default")
      (node (ref "K14") (pin "1") (pinfunction "Comum_1") (pintype "passive"))
      (node (ref "N14") (pin "1") (pinfunction "1_1") (pintype "passive"))
    )
    (net (code "62") (name "Net-(K14-N.A.)") (class "Default")
      (node (ref "K14") (pin "2") (pinfunction "N.A._2") (pintype "passive"))
      (node (ref "M14") (pin "1") (pinfunction "1_1") (pintype "passive"))
    )
    (net (code "63") (name "Net-(K15-Comum)") (class "Default")
      (node (ref "K15") (pin "1") (pinfunction "Comum_1") (pintype "passive"))
      (node (ref "N15") (pin "1") (pinfunction "1_1") (pintype "passive"))
    )
    (net (code "64") (name "Net-(K15-N.A.)") (class "Default")
      (node (ref "K15") (pin "2") (pinfunction "N.A._2") (pintype "passive"))
      (node (ref "M15") (pin "1") (pinfunction "1_1") (pintype "passive"))
    )
    (net (code "65") (name "Net-(K16-Comum)") (class "Default")
      (node (ref "K16") (pin "1") (pinfunction "Comum_1") (pintype "passive"))
      (node (ref "N16") (pin "1") (pinfunction "1_1") (pintype "passive"))
    )
    (net (code "66") (name "Net-(K16-N.A.)") (class "Default")
      (node (ref "K16") (pin "2") (pinfunction "N.A._2") (pintype "passive"))
      (node (ref "M16") (pin "1") (pinfunction "1_1") (pintype "passive"))
    )
    (net (code "67") (name "Net-(Q1-B)") (class "Default")
      (node (ref "Q1") (pin "1") (pinfunction "B_1") (pintype "passive"))
      (node (ref "R3") (pin "2") (pinfunction "2_2") (pintype "passive"))
    )
    (net (code "68") (name "Net-(Q2-B)") (class "Default")
      (node (ref "Q2") (pin "1") (pinfunction "B_1") (pintype "passive"))
      (node (ref "R4") (pin "2") (pinfunction "2_2") (pintype "passive"))
    )
    (net (code "69") (name "Net-(Q3-B)") (class "Default")
      (node (ref "Q3") (pin "1") (pinfunction "B_1") (pintype "passive"))
      (node (ref "R5") (pin "2") (pinfunction "2_2") (pintype "passive"))
    )
    (net (code "70") (name "Net-(Q4-B)") (class "Default")
      (node (ref "Q4") (pin "1") (pinfunction "B_1") (pintype "passive"))
      (node (ref "R6") (pin "2") (pinfunction "2_2") (pintype "passive"))
    )
    (net (code "71") (name "Net-(Q5-B)") (class "Default")
      (node (ref "Q5") (pin "1") (pinfunction "B_1") (pintype "passive"))
      (node (ref "R7") (pin "2") (pinfunction "2_2") (pintype "passive"))
    )
    (net (code "72") (name "Net-(Q6-B)") (class "Default")
      (node (ref "Q6") (pin "1") (pinfunction "B_1") (pintype "passive"))
      (node (ref "R8") (pin "2") (pinfunction "2_2") (pintype "passive"))
    )
    (net (code "73") (name "Net-(Q7-B)") (class "Default")
      (node (ref "Q7") (pin "1") (pinfunction "B_1") (pintype "passive"))
      (node (ref "R9") (pin "2") (pinfunction "2_2") (pintype "passive"))
    )
    (net (code "74") (name "Net-(Q8-B)") (class "Default")
      (node (ref "Q8") (pin "1") (pinfunction "B_1") (pintype "passive"))
      (node (ref "R10") (pin "2") (pinfunction "2_2") (pintype "passive"))
    )
    (net (code "75") (name "Net-(Q9-B)") (class "Default")
      (node (ref "Q9") (pin "1") (pinfunction "B_1") (pintype "passive"))
      (node (ref "R11") (pin "2") (pinfunction "2_2") (pintype "passive"))
    )
    (net (code "76") (name "Net-(Q10-B)") (class "Default")
      (node (ref "Q10") (pin "1") (pinfunction "B_1") (pintype "passive"))
      (node (ref "R12") (pin "2") (pinfunction "2_2") (pintype "passive"))
    )
    (net (code "77") (name "Net-(Q11-B)") (class "Default")
      (node (ref "Q11") (pin "1") (pinfunction "B_1") (pintype "passive"))
      (node (ref "R13") (pin "2") (pinfunction "2_2") (pintype "passive"))
    )
    (net (code "78") (name "Net-(Q12-B)") (class "Default")
      (node (ref "Q12") (pin "1") (pinfunction "B_1") (pintype "passive"))
      (node (ref "R14") (pin "2") (pinfunction "2_2") (pintype "passive"))
    )
    (net (code "79") (name "Net-(Q13-B)") (class "Default")
      (node (ref "Q13") (pin "1") (pinfunction "B_1") (pintype "passive"))
      (node (ref "R15") (pin "2") (pinfunction "2_2") (pintype "passive"))
    )
    (net (code "80") (name "Net-(Q14-B)") (class "Default")
      (node (ref "Q14") (pin "1") (pinfunction "B_1") (pintype "passive"))
      (node (ref "R16") (pin "2") (pinfunction "2_2") (pintype "passive"))
    )
    (net (code "81") (name "Net-(Q15-B)") (class "Default")
      (node (ref "Q15") (pin "1") (pinfunction "B_1") (pintype "passive"))
      (node (ref "R17") (pin "2") (pinfunction "2_2") (pintype "passive"))
    )
    (net (code "82") (name "Net-(Q16-B)") (class "Default")
      (node (ref "Q16") (pin "1") (pinfunction "B_1") (pintype "passive"))
      (node (ref "R18") (pin "2") (pinfunction "2_2") (pintype "passive"))
    )
    (net (code "83") (name "unconnected-(K1-N.F.-Pad3)") (class "Default")
      (node (ref "K1") (pin "3") (pinfunction "N.F._3") (pintype "passive"))
    )
    (net (code "84") (name "unconnected-(K2-N.F.-Pad3)") (class "Default")
      (node (ref "K2") (pin "3") (pinfunction "N.F._3") (pintype "passive"))
    )
    (net (code "85") (name "unconnected-(K3-N.F.-Pad3)") (class "Default")
      (node (ref "K3") (pin "3") (pinfunction "N.F._3") (pintype "passive"))
    )
    (net (code "86") (name "unconnected-(K4-N.F.-Pad3)") (class "Default")
      (node (ref "K4") (pin "3") (pinfunction "N.F._3") (pintype "passive"))
    )
    (net (code "87") (name "unconnected-(K5-N.F.-Pad3)") (class "Default")
      (node (ref "K5") (pin "3") (pinfunction "N.F._3") (pintype "passive"))
    )
    (net (code "88") (name "unconnected-(K6-N.F.-Pad3)") (class "Default")
      (node (ref "K6") (pin "3") (pinfunction "N.F._3") (pintype "passive"))
    )
    (net (code "89") (name "unconnected-(K7-N.F.-Pad3)") (class "Default")
      (node (ref "K7") (pin "3") (pinfunction "N.F._3") (pintype "passive"))
    )
    (net (code "90") (name "unconnected-(K8-N.F.-Pad3)") (class "Default")
      (node (ref "K8") (pin "3") (pinfunction "N.F._3") (pintype "passive"))
    )
    (net (code "91") (name "unconnected-(K9-N.F.-Pad3)") (class "Default")
      (node (ref "K9") (pin "3") (pinfunction "N.F._3") (pintype "passive"))
    )
    (net (code "92") (name "unconnected-(K10-N.F.-Pad3)") (class "Default")
      (node (ref "K10") (pin "3") (pinfunction "N.F._3") (pintype "passive"))
    )
    (net (code "93") (name "unconnected-(K11-N.F.-Pad3)") (class "Default")
      (node (ref "K11") (pin "3") (pinfunction "N.F._3") (pintype "passive"))
    )
    (net (code "94") (name "unconnected-(K12-N.F.-Pad3)") (class "Default")
      (node (ref "K12") (pin "3") (pinfunction "N.F._3") (pintype "passive"))
    )
    (net (code "95") (name "unconnected-(K13-N.F.-Pad3)") (class "Default")
      (node (ref "K13") (pin "3") (pinfunction "N.F._3") (pintype "passive"))
    )
    (net (code "96") (name "unconnected-(K14-N.F.-Pad3)") (class "Default")
      (node (ref "K14") (pin "3") (pinfunction "N.F._3") (pintype "passive"))
    )
    (net (code "97") (name "unconnected-(K15-N.F.-Pad3)") (class "Default")
      (node (ref "K15") (pin "3") (pinfunction "N.F._3") (pintype "passive"))
    )
    (net (code "98") (name "unconnected-(K16-N.F.-Pad3)") (class "Default")
      (node (ref "K16") (pin "3") (pinfunction "N.F._3") (pintype "passive"))
    )
  )
)
